# Interfaces.net
KiCad netlist of a schematic drawn in Altium Designer
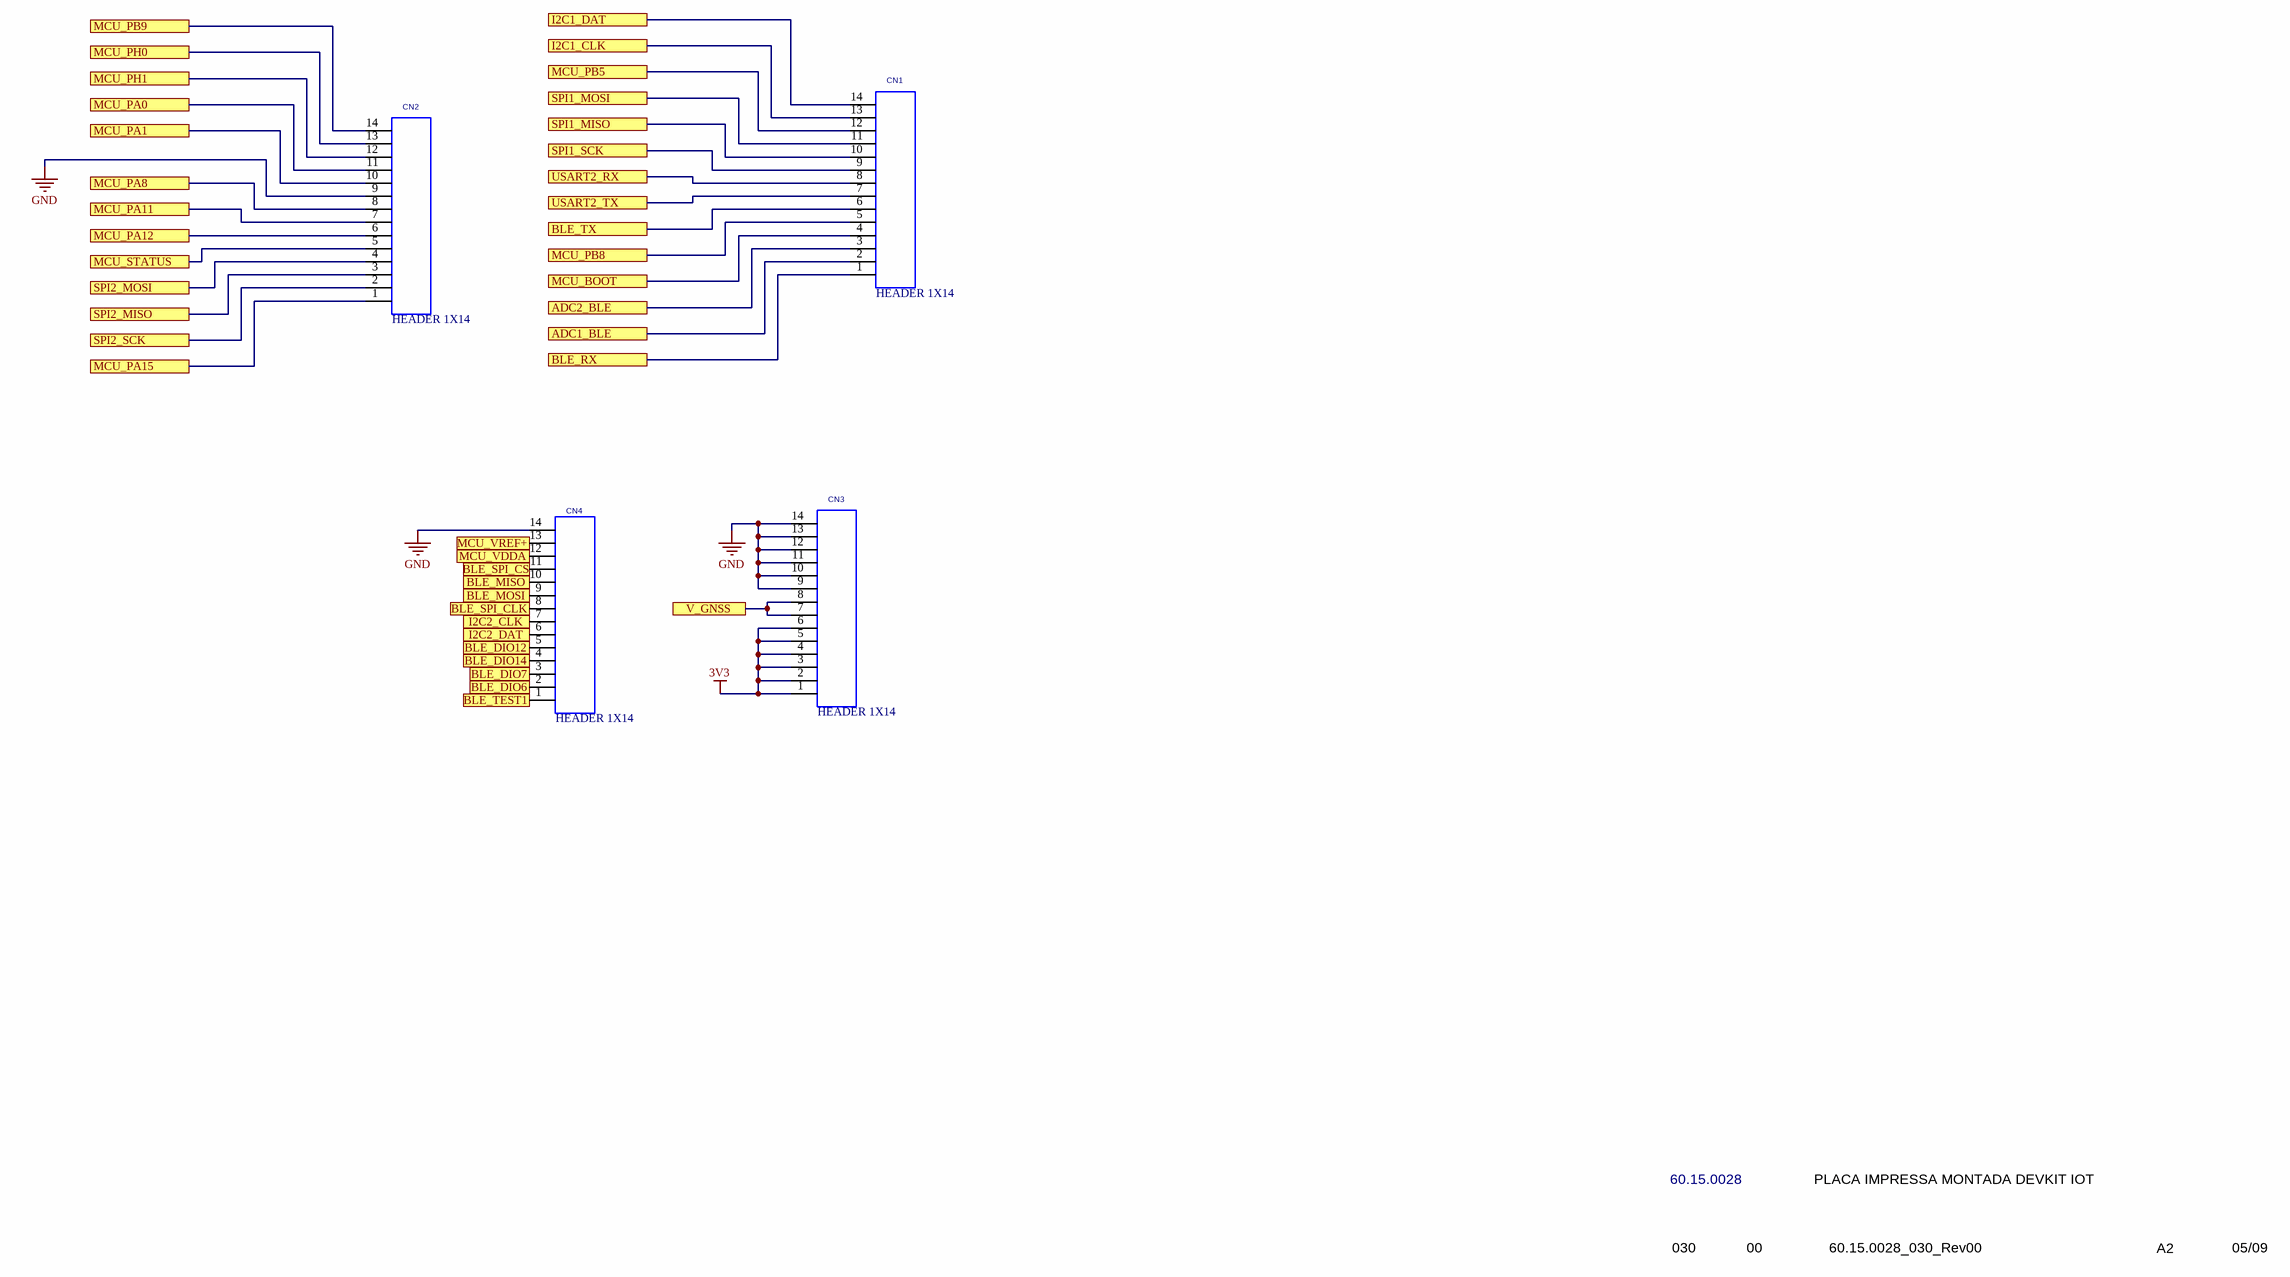
[diagram p0: Interfaces.SchDoc]

(export (version "E")
  (design (tool "Eeschema 10.0.6"))
  (components
    (comp (ref "CN1")
      (value "28.14.0551")
      (footprint "28.14.0551")
      (description "CONECTOR HEADER FM 14 VIAS 180G P/PCB")
      (fields (field (name "ALTIUM_UNNAMED_1") "HEADER 1X14"))
      (libsource (lib "OMNI-CONECTORES") (part "28.14.0551"))
    )
    (comp (ref "CN2")
      (value "28.14.0551")
      (footprint "28.14.0551")
      (description "CONECTOR HEADER FM 14 VIAS 180G P/PCB")
      (fields (field (name "ALTIUM_UNNAMED_1") "HEADER 1X14"))
      (libsource (lib "OMNI-CONECTORES") (part "28.14.0551"))
    )
    (comp (ref "CN3")
      (value "28.14.0551")
      (footprint "28.14.0551")
      (description "CONECTOR HEADER FM 14 VIAS 180G P/PCB")
      (fields (field (name "ALTIUM_UNNAMED_1") "HEADER 1X14"))
      (libsource (lib "OMNI-CONECTORES") (part "28.14.0551"))
    )
    (comp (ref "CN4")
      (value "28.14.0551")
      (footprint "28.14.0551")
      (description "CONECTOR HEADER FM 14 VIAS 180G P/PCB")
      (fields (field (name "ALTIUM_UNNAMED_1") "HEADER 1X14"))
      (libsource (lib "OMNI-CONECTORES") (part "28.14.0551"))
    )
  )
  (nets
    (net (code "1") (name "/ADC1_BLE") (class "Default")
      (node (ref "CN1") (pin "2") (pinfunction "2_2") (pintype "passive"))
    )
    (net (code "2") (name "/ADC2_BLE") (class "Default")
      (node (ref "CN1") (pin "3") (pinfunction "3_3") (pintype "passive"))
    )
    (net (code "3") (name "/BLE_DIO6") (class "Default")
      (node (ref "CN4") (pin "2") (pinfunction "2_2") (pintype "passive"))
    )
    (net (code "4") (name "/BLE_DIO7") (class "Default")
      (node (ref "CN4") (pin "3") (pinfunction "3_3") (pintype "passive"))
    )
    (net (code "5") (name "/BLE_DIO12") (class "Default")
      (node (ref "CN4") (pin "5") (pinfunction "5_5") (pintype "passive"))
    )
    (net (code "6") (name "/BLE_DIO14") (class "Default")
      (node (ref "CN4") (pin "4") (pinfunction "4_4") (pintype "passive"))
    )
    (net (code "7") (name "/BLE_MISO") (class "Default")
      (node (ref "CN4") (pin "10") (pinfunction "10_10") (pintype "passive"))
    )
    (net (code "8") (name "/BLE_MOSI") (class "Default")
      (node (ref "CN4") (pin "9") (pinfunction "9_9") (pintype "passive"))
    )
    (net (code "9") (name "/BLE_RX") (class "Default")
      (node (ref "CN1") (pin "1") (pinfunction "1_1") (pintype "passive"))
    )
    (net (code "10") (name "/BLE_SPI_CLK") (class "Default")
      (node (ref "CN4") (pin "8") (pinfunction "8_8") (pintype "passive"))
    )
    (net (code "11") (name "/BLE_SPI_CS") (class "Default")
      (node (ref "CN4") (pin "11") (pinfunction "11_11") (pintype "passive"))
    )
    (net (code "12") (name "/BLE_TEST1") (class "Default")
      (node (ref "CN4") (pin "1") (pinfunction "1_1") (pintype "passive"))
    )
    (net (code "13") (name "/BLE_TX") (class "Default")
      (node (ref "CN1") (pin "6") (pinfunction "6_6") (pintype "passive"))
    )
    (net (code "14") (name "/I2C1_CLK") (class "Default")
      (node (ref "CN1") (pin "13") (pinfunction "13_13") (pintype "passive"))
    )
    (net (code "15") (name "/I2C1_DAT") (class "Default")
      (node (ref "CN1") (pin "14") (pinfunction "14_14") (pintype "passive"))
    )
    (net (code "16") (name "/I2C2_CLK") (class "Default")
      (node (ref "CN4") (pin "7") (pinfunction "7_7") (pintype "passive"))
    )
    (net (code "17") (name "/I2C2_DAT") (class "Default")
      (node (ref "CN4") (pin "6") (pinfunction "6_6") (pintype "passive"))
    )
    (net (code "18") (name "/MCU_BOOT") (class "Default")
      (node (ref "CN1") (pin "4") (pinfunction "4_4") (pintype "passive"))
    )
    (net (code "19") (name "/MCU_PA0") (class "Default")
      (node (ref "CN2") (pin "11") (pinfunction "11_11") (pintype "passive"))
    )
    (net (code "20") (name "/MCU_PA1") (class "Default")
      (node (ref "CN2") (pin "10") (pinfunction "10_10") (pintype "passive"))
    )
    (net (code "21") (name "/MCU_PA8") (class "Default")
      (node (ref "CN2") (pin "8") (pinfunction "8_8") (pintype "passive"))
    )
    (net (code "22") (name "/MCU_PA11") (class "Default")
      (node (ref "CN2") (pin "7") (pinfunction "7_7") (pintype "passive"))
    )
    (net (code "23") (name "/MCU_PA12") (class "Default")
      (node (ref "CN2") (pin "6") (pinfunction "6_6") (pintype "passive"))
    )
    (net (code "24") (name "/MCU_PA15") (class "Default")
      (node (ref "CN2") (pin "1") (pinfunction "1_1") (pintype "passive"))
    )
    (net (code "25") (name "/MCU_PB5") (class "Default")
      (node (ref "CN1") (pin "12") (pinfunction "12_12") (pintype "passive"))
    )
    (net (code "26") (name "/MCU_PB8") (class "Default")
      (node (ref "CN1") (pin "5") (pinfunction "5_5") (pintype "passive"))
    )
    (net (code "27") (name "/MCU_PB9") (class "Default")
      (node (ref "CN2") (pin "14") (pinfunction "14_14") (pintype "passive"))
    )
    (net (code "28") (name "/MCU_PH0") (class "Default")
      (node (ref "CN2") (pin "13") (pinfunction "13_13") (pintype "passive"))
    )
    (net (code "29") (name "/MCU_PH1") (class "Default")
      (node (ref "CN2") (pin "12") (pinfunction "12_12") (pintype "passive"))
    )
    (net (code "30") (name "/MCU_STATUS") (class "Default")
      (node (ref "CN2") (pin "5") (pinfunction "5_5") (pintype "passive"))
    )
    (net (code "31") (name "/MCU_VDDA") (class "Default")
      (node (ref "CN4") (pin "12") (pinfunction "12_12") (pintype "passive"))
    )
    (net (code "32") (name "/MCU_VREF+") (class "Default")
      (node (ref "CN4") (pin "13") (pinfunction "13_13") (pintype "passive"))
    )
    (net (code "33") (name "/SPI1_MISO") (class "Default")
      (node (ref "CN1") (pin "10") (pinfunction "10_10") (pintype "passive"))
    )
    (net (code "34") (name "/SPI1_MOSI") (class "Default")
      (node (ref "CN1") (pin "11") (pinfunction "11_11") (pintype "passive"))
    )
    (net (code "35") (name "/SPI1_SCK") (class "Default")
      (node (ref "CN1") (pin "9") (pinfunction "9_9") (pintype "passive"))
    )
    (net (code "36") (name "/SPI2_MISO") (class "Default")
      (node (ref "CN2") (pin "3") (pinfunction "3_3") (pintype "passive"))
    )
    (net (code "37") (name "/SPI2_MOSI") (class "Default")
      (node (ref "CN2") (pin "4") (pinfunction "4_4") (pintype "passive"))
    )
    (net (code "38") (name "/SPI2_SCK") (class "Default")
      (node (ref "CN2") (pin "2") (pinfunction "2_2") (pintype "passive"))
    )
    (net (code "39") (name "/USART2_RX") (class "Default")
      (node (ref "CN1") (pin "8") (pinfunction "8_8") (pintype "passive"))
    )
    (net (code "40") (name "/USART2_TX") (class "Default")
      (node (ref "CN1") (pin "7") (pinfunction "7_7") (pintype "passive"))
    )
    (net (code "41") (name "/V_GNSS") (class "Default")
      (node (ref "CN3") (pin "7") (pinfunction "7_7") (pintype "passive"))
      (node (ref "CN3") (pin "8") (pinfunction "8_8") (pintype "passive"))
    )
    (net (code "42") (name "3V3") (class "Default")
      (node (ref "CN3") (pin "1") (pinfunction "1_1") (pintype "passive"))
      (node (ref "CN3") (pin "2") (pinfunction "2_2") (pintype "passive"))
      (node (ref "CN3") (pin "3") (pinfunction "3_3") (pintype "passive"))
      (node (ref "CN3") (pin "4") (pinfunction "4_4") (pintype "passive"))
      (node (ref "CN3") (pin "5") (pinfunction "5_5") (pintype "passive"))
      (node (ref "CN3") (pin "6") (pinfunction "6_6") (pintype "passive"))
    )
    (net (code "43") (name "GND") (class "Default")
      (node (ref "CN2") (pin "9") (pinfunction "9_9") (pintype "passive"))
      (node (ref "CN3") (pin "10") (pinfunction "10_10") (pintype "passive"))
      (node (ref "CN3") (pin "11") (pinfunction "11_11") (pintype "passive"))
      (node (ref "CN3") (pin "12") (pinfunction "12_12") (pintype "passive"))
      (node (ref "CN3") (pin "13") (pinfunction "13_13") (pintype "passive"))
      (node (ref "CN3") (pin "14") (pinfunction "14_14") (pintype "passive"))
      (node (ref "CN3") (pin "9") (pinfunction "9_9") (pintype "passive"))
      (node (ref "CN4") (pin "14") (pinfunction "14_14") (pintype "passive"))
    )
  )
)
